# MOTOR_DRIVER.net
KiCad netlist of a schematic drawn in Altium Designer
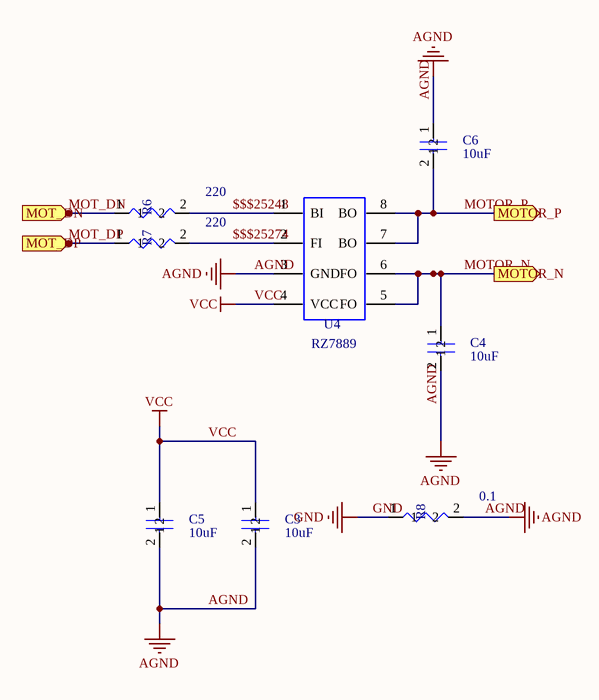
[diagram p0: MOTOR_DRIVER.SchDoc]

(export (version "E")
  (design (tool "Eeschema 10.0.6"))
  (components
    (comp (ref "C3")
      (value "10uF")
      (fields (field (name "Comment") "EC0603"))
      (libsource (lib "*") (part "EC0603"))
    )
    (comp (ref "C4")
      (value "10uF")
      (fields (field (name "Comment") "EC0603"))
      (libsource (lib "*") (part "EC0603"))
    )
    (comp (ref "C5")
      (value "10uF")
      (fields (field (name "Comment") "EC0603"))
      (libsource (lib "*") (part "EC0603"))
    )
    (comp (ref "C6")
      (value "10uF")
      (fields (field (name "Comment") "EC0603"))
      (libsource (lib "*") (part "EC0603"))
    )
    (comp (ref "R6")
      (value "220")
      (description "RES,thick film,47KOhm,+/-5%,1/16W,SMD0402")
      (fields (field (name "Comment") "RESISTOR"))
      (libsource (lib "*") (part "RESISTOR"))
    )
    (comp (ref "R7")
      (value "220")
      (description "RES,thick film,47KOhm,+/-5%,1/16W,SMD0402")
      (fields (field (name "Comment") "RESISTOR"))
      (libsource (lib "*") (part "RESISTOR"))
    )
    (comp (ref "R8")
      (value "0.1")
      (description "RES,thick film,47KOhm,+/-5%,1/16W,SMD0402")
      (fields (field (name "Comment") "RESISTOR"))
      (libsource (lib "*") (part "RESISTOR"))
    )
    (comp (ref "U4") (value "RZ7889") (libsource (lib "*") (part "RZ7889")))
  )
  (nets
    (net (code "1") (name "/$$$25248") (class "Default")
      (node (ref "R6") (pin "2") (pinfunction "2_2") (pintype "passive"))
      (node (ref "U4") (pin "1") (pinfunction "BI_1") (pintype "passive"))
    )
    (net (code "2") (name "/$$$25274") (class "Default")
      (node (ref "R7") (pin "2") (pinfunction "2_2") (pintype "passive"))
      (node (ref "U4") (pin "2") (pinfunction "FI_2") (pintype "passive"))
    )
    (net (code "3") (name "/MOTOR_N") (class "Default")
      (node (ref "C4") (pin "1") (pinfunction "1_1") (pintype "passive"))
      (node (ref "U4") (pin "5") (pinfunction "FO_5") (pintype "passive"))
      (node (ref "U4") (pin "6") (pinfunction "FO_6") (pintype "passive"))
    )
    (net (code "4") (name "/MOTOR_P") (class "Default")
      (node (ref "C6") (pin "2") (pinfunction "2_2") (pintype "passive"))
      (node (ref "U4") (pin "7") (pinfunction "BO_7") (pintype "passive"))
      (node (ref "U4") (pin "8") (pinfunction "BO_8") (pintype "passive"))
    )
    (net (code "5") (name "/MOT_DN") (class "Default")
      (node (ref "R6") (pin "1") (pinfunction "1_1") (pintype "passive"))
    )
    (net (code "6") (name "/MOT_DP") (class "Default")
      (node (ref "R7") (pin "1") (pinfunction "1_1") (pintype "passive"))
    )
    (net (code "7") (name "AGND") (class "Default")
      (node (ref "C3") (pin "2") (pinfunction "2_2") (pintype "passive"))
      (node (ref "C4") (pin "2") (pinfunction "2_2") (pintype "passive"))
      (node (ref "C5") (pin "2") (pinfunction "2_2") (pintype "passive"))
      (node (ref "C6") (pin "1") (pinfunction "1_1") (pintype "passive"))
      (node (ref "R8") (pin "2") (pinfunction "2_2") (pintype "passive"))
      (node (ref "U4") (pin "3") (pinfunction "GND_3") (pintype "passive"))
    )
    (net (code "8") (name "GND") (class "Default")
      (node (ref "R8") (pin "1") (pinfunction "1_1") (pintype "passive"))
    )
    (net (code "9") (name "VCC") (class "Default")
      (node (ref "C3") (pin "1") (pinfunction "1_1") (pintype "passive"))
      (node (ref "C5") (pin "1") (pinfunction "1_1") (pintype "passive"))
      (node (ref "U4") (pin "4") (pinfunction "VCC_4") (pintype "passive"))
    )
  )
)
